# con-left-top.net
KiCad netlist of a schematic drawn in Altium Designer
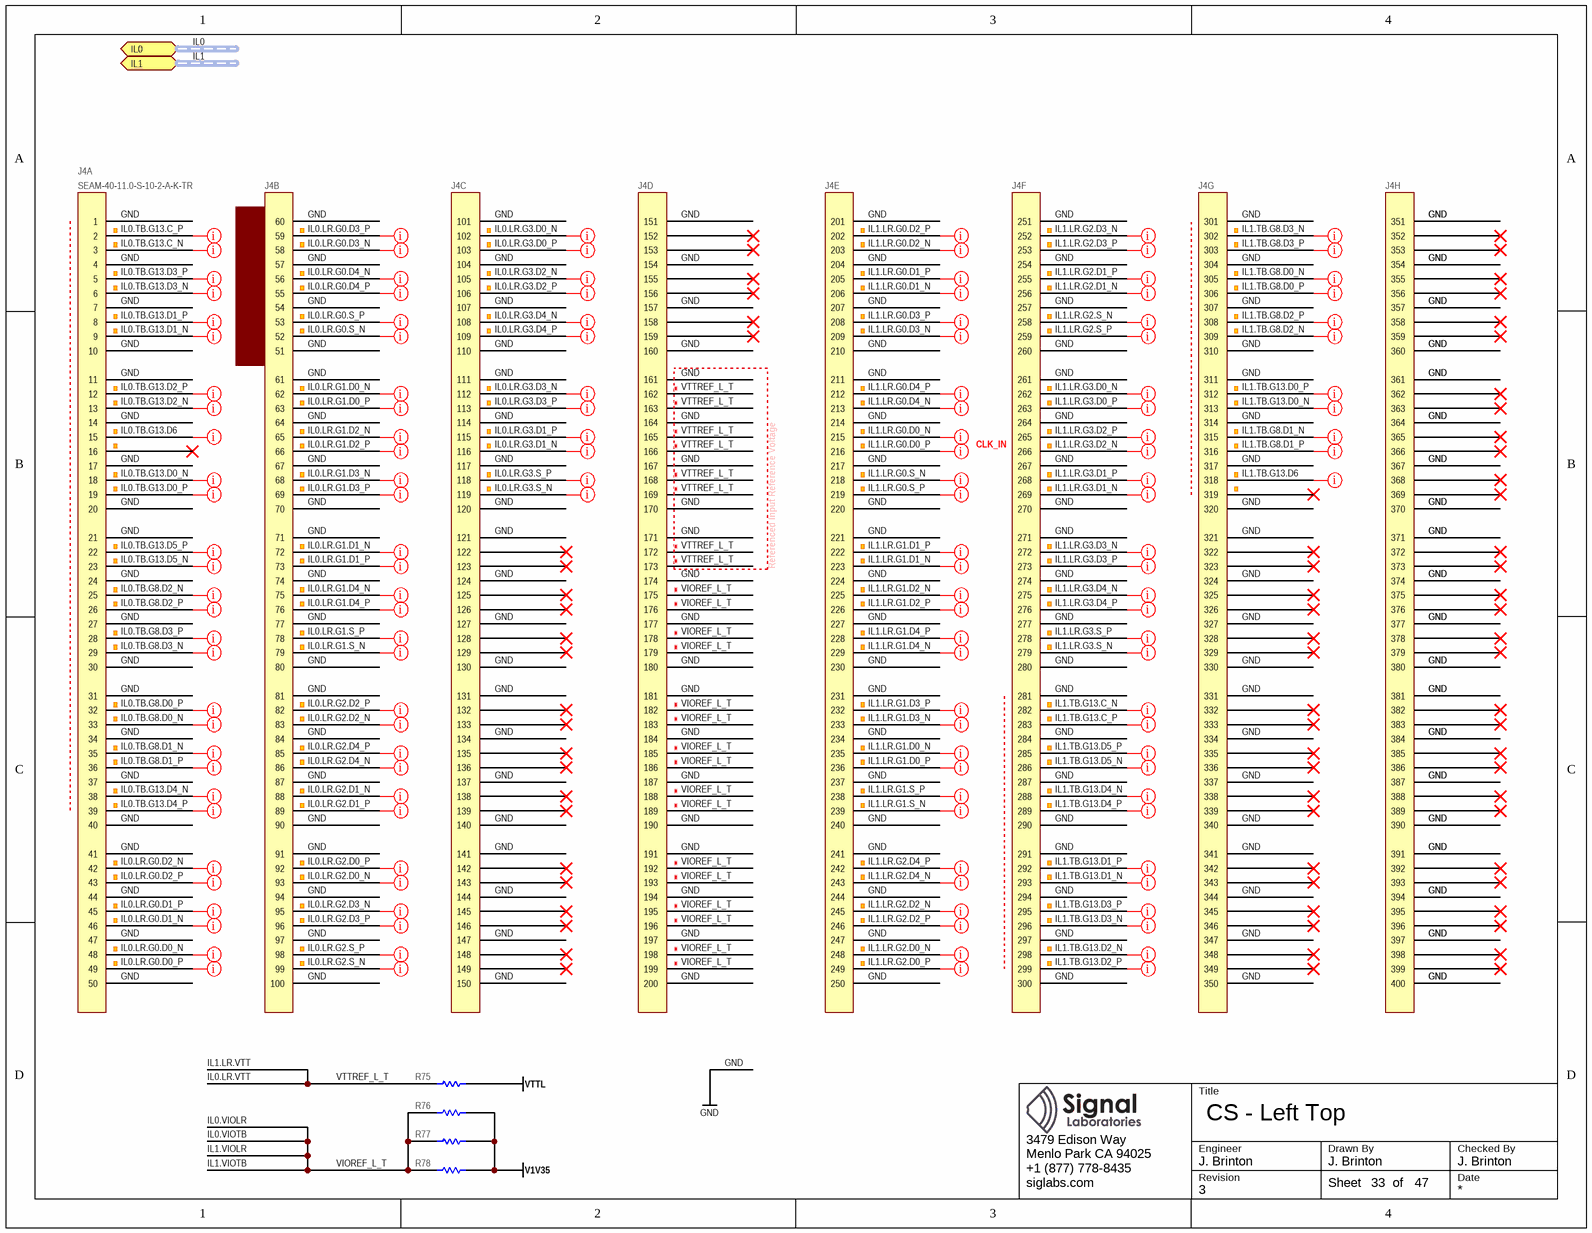
[diagram p0: con-left-top.SchDoc]

(export (version "E")
  (design (tool "Eeschema 10.0.6"))
  (components
    (comp (ref "J4")
      (value "SEAM-40-11.0-S-10-2-A-K-TR")
      (footprint "samtec:SEAM-40-11.0-S-10-2-A-K-TR")
      (description "Terminal Array Assembly, Surface Mount, 0.050\" Pitch, 400 Pins")
      (fields (field (name "MANUFACTURER") "Samtec"))
      (libsource (lib "samtec") (part "SEAM-40-11.0-S-10-2-A-K-TR"))
    )
    (comp (ref "R75")
      (value "SOLDER_LINK")
      (footprint "SOLDERLINK0603X26N")
      (description "Solder Link")
      (libsource (lib "generic") (part "RES"))
    )
    (comp (ref "R76")
      (value "SOLDER_LINK")
      (footprint "SOLDERLINK0603X26N")
      (description "Solder Link")
      (libsource (lib "generic") (part "RES"))
    )
    (comp (ref "R77")
      (value "SOLDER_LINK")
      (footprint "SOLDERLINK0603X26N")
      (description "Solder Link")
      (libsource (lib "generic") (part "RES"))
    )
    (comp (ref "R78")
      (value "SOLDER_LINK")
      (footprint "SOLDERLINK0603X26N")
      (description "Solder Link")
      (libsource (lib "generic") (part "RES"))
    )
  )
  (nets
    (net (code "3") (name "/IL0.LR.G0.D0_N") (class "Default")
      (node (ref "J4") (pin "48") (pinfunction "48_48") (pintype "passive"))
    )
    (net (code "4") (name "/IL0.LR.G0.D0_P") (class "Default")
      (node (ref "J4") (pin "49") (pinfunction "49_49") (pintype "passive"))
    )
    (net (code "5") (name "/IL0.LR.G0.D1_N") (class "Default")
      (node (ref "J4") (pin "46") (pinfunction "46_46") (pintype "passive"))
    )
    (net (code "6") (name "/IL0.LR.G0.D1_P") (class "Default")
      (node (ref "J4") (pin "45") (pinfunction "45_45") (pintype "passive"))
    )
    (net (code "7") (name "/IL0.LR.G0.D2_N") (class "Default")
      (node (ref "J4") (pin "42") (pinfunction "42_42") (pintype "passive"))
    )
    (net (code "8") (name "/IL0.LR.G0.D2_P") (class "Default")
      (node (ref "J4") (pin "43") (pinfunction "43_43") (pintype "passive"))
    )
    (net (code "9") (name "/IL0.LR.G0.D3_N") (class "Default")
      (node (ref "J4") (pin "58") (pinfunction "58_58") (pintype "passive"))
    )
    (net (code "10") (name "/IL0.LR.G0.D3_P") (class "Default")
      (node (ref "J4") (pin "59") (pinfunction "59_59") (pintype "passive"))
    )
    (net (code "11") (name "/IL0.LR.G0.D4_N") (class "Default")
      (node (ref "J4") (pin "56") (pinfunction "56_56") (pintype "passive"))
    )
    (net (code "12") (name "/IL0.LR.G0.D4_P") (class "Default")
      (node (ref "J4") (pin "55") (pinfunction "55_55") (pintype "passive"))
    )
    (net (code "13") (name "/IL0.LR.G0.S_N") (class "Default")
      (node (ref "J4") (pin "52") (pinfunction "52_52") (pintype "passive"))
    )
    (net (code "14") (name "/IL0.LR.G0.S_P") (class "Default")
      (node (ref "J4") (pin "53") (pinfunction "53_53") (pintype "passive"))
    )
    (net (code "15") (name "/IL0.LR.G1.D0_N") (class "Default")
      (node (ref "J4") (pin "62") (pinfunction "62_62") (pintype "passive"))
    )
    (net (code "16") (name "/IL0.LR.G1.D0_P") (class "Default")
      (node (ref "J4") (pin "63") (pinfunction "63_63") (pintype "passive"))
    )
    (net (code "17") (name "/IL0.LR.G1.D1_N") (class "Default")
      (node (ref "J4") (pin "72") (pinfunction "72_72") (pintype "passive"))
    )
    (net (code "18") (name "/IL0.LR.G1.D1_P") (class "Default")
      (node (ref "J4") (pin "73") (pinfunction "73_73") (pintype "passive"))
    )
    (net (code "19") (name "/IL0.LR.G1.D2_N") (class "Default")
      (node (ref "J4") (pin "65") (pinfunction "65_65") (pintype "passive"))
    )
    (net (code "20") (name "/IL0.LR.G1.D2_P") (class "Default")
      (node (ref "J4") (pin "66") (pinfunction "66_66") (pintype "passive"))
    )
    (net (code "21") (name "/IL0.LR.G1.D3_N") (class "Default")
      (node (ref "J4") (pin "68") (pinfunction "68_68") (pintype "passive"))
    )
    (net (code "22") (name "/IL0.LR.G1.D3_P") (class "Default")
      (node (ref "J4") (pin "69") (pinfunction "69_69") (pintype "passive"))
    )
    (net (code "23") (name "/IL0.LR.G1.D4_N") (class "Default")
      (node (ref "J4") (pin "75") (pinfunction "75_75") (pintype "passive"))
    )
    (net (code "24") (name "/IL0.LR.G1.D4_P") (class "Default")
      (node (ref "J4") (pin "76") (pinfunction "76_76") (pintype "passive"))
    )
    (net (code "25") (name "/IL0.LR.G1.S_N") (class "Default")
      (node (ref "J4") (pin "79") (pinfunction "79_79") (pintype "passive"))
    )
    (net (code "26") (name "/IL0.LR.G1.S_P") (class "Default")
      (node (ref "J4") (pin "78") (pinfunction "78_78") (pintype "passive"))
    )
    (net (code "27") (name "/IL0.LR.G2.D0_N") (class "Default")
      (node (ref "J4") (pin "93") (pinfunction "93_93") (pintype "passive"))
    )
    (net (code "28") (name "/IL0.LR.G2.D0_P") (class "Default")
      (node (ref "J4") (pin "92") (pinfunction "92_92") (pintype "passive"))
    )
    (net (code "29") (name "/IL0.LR.G2.D1_N") (class "Default")
      (node (ref "J4") (pin "88") (pinfunction "88_88") (pintype "passive"))
    )
    (net (code "30") (name "/IL0.LR.G2.D1_P") (class "Default")
      (node (ref "J4") (pin "89") (pinfunction "89_89") (pintype "passive"))
    )
    (net (code "31") (name "/IL0.LR.G2.D2_N") (class "Default")
      (node (ref "J4") (pin "83") (pinfunction "83_83") (pintype "passive"))
    )
    (net (code "32") (name "/IL0.LR.G2.D2_P") (class "Default")
      (node (ref "J4") (pin "82") (pinfunction "82_82") (pintype "passive"))
    )
    (net (code "33") (name "/IL0.LR.G2.D3_N") (class "Default")
      (node (ref "J4") (pin "95") (pinfunction "95_95") (pintype "passive"))
    )
    (net (code "34") (name "/IL0.LR.G2.D3_P") (class "Default")
      (node (ref "J4") (pin "96") (pinfunction "96_96") (pintype "passive"))
    )
    (net (code "35") (name "/IL0.LR.G2.D4_N") (class "Default")
      (node (ref "J4") (pin "86") (pinfunction "86_86") (pintype "passive"))
    )
    (net (code "36") (name "/IL0.LR.G2.D4_P") (class "Default")
      (node (ref "J4") (pin "85") (pinfunction "85_85") (pintype "passive"))
    )
    (net (code "37") (name "/IL0.LR.G2.S_N") (class "Default")
      (node (ref "J4") (pin "99") (pinfunction "99_99") (pintype "passive"))
    )
    (net (code "38") (name "/IL0.LR.G2.S_P") (class "Default")
      (node (ref "J4") (pin "98") (pinfunction "98_98") (pintype "passive"))
    )
    (net (code "39") (name "/IL0.LR.G3.D0_N") (class "Default")
      (node (ref "J4") (pin "102") (pinfunction "102_102") (pintype "passive"))
    )
    (net (code "40") (name "/IL0.LR.G3.D0_P") (class "Default")
      (node (ref "J4") (pin "103") (pinfunction "103_103") (pintype "passive"))
    )
    (net (code "41") (name "/IL0.LR.G3.D1_N") (class "Default")
      (node (ref "J4") (pin "116") (pinfunction "116_116") (pintype "passive"))
    )
    (net (code "42") (name "/IL0.LR.G3.D1_P") (class "Default")
      (node (ref "J4") (pin "115") (pinfunction "115_115") (pintype "passive"))
    )
    (net (code "43") (name "/IL0.LR.G3.D2_N") (class "Default")
      (node (ref "J4") (pin "105") (pinfunction "105_105") (pintype "passive"))
    )
    (net (code "44") (name "/IL0.LR.G3.D2_P") (class "Default")
      (node (ref "J4") (pin "106") (pinfunction "106_106") (pintype "passive"))
    )
    (net (code "45") (name "/IL0.LR.G3.D3_N") (class "Default")
      (node (ref "J4") (pin "112") (pinfunction "112_112") (pintype "passive"))
    )
    (net (code "46") (name "/IL0.LR.G3.D3_P") (class "Default")
      (node (ref "J4") (pin "113") (pinfunction "113_113") (pintype "passive"))
    )
    (net (code "47") (name "/IL0.LR.G3.D4_N") (class "Default")
      (node (ref "J4") (pin "108") (pinfunction "108_108") (pintype "passive"))
    )
    (net (code "48") (name "/IL0.LR.G3.D4_P") (class "Default")
      (node (ref "J4") (pin "109") (pinfunction "109_109") (pintype "passive"))
    )
    (net (code "49") (name "/IL0.LR.G3.S_N") (class "Default")
      (node (ref "J4") (pin "119") (pinfunction "119_119") (pintype "passive"))
    )
    (net (code "50") (name "/IL0.LR.G3.S_P") (class "Default")
      (node (ref "J4") (pin "118") (pinfunction "118_118") (pintype "passive"))
    )
    (net (code "51") (name "/IL0.LR.VTT") (class "Default")
      (node (ref "J4") (pin "162") (pinfunction "162_162") (pintype "passive"))
      (node (ref "J4") (pin "163") (pinfunction "163_163") (pintype "passive"))
      (node (ref "J4") (pin "165") (pinfunction "165_165") (pintype "passive"))
      (node (ref "J4") (pin "166") (pinfunction "166_166") (pintype "passive"))
      (node (ref "J4") (pin "168") (pinfunction "168_168") (pintype "passive"))
      (node (ref "J4") (pin "169") (pinfunction "169_169") (pintype "passive"))
      (node (ref "J4") (pin "172") (pinfunction "172_172") (pintype "passive"))
      (node (ref "J4") (pin "173") (pinfunction "173_173") (pintype "passive"))
      (node (ref "R75") (pin "2") (pinfunction "2_2") (pintype "passive"))
    )
    (net (code "52") (name "/IL0.TB.G8.D0_N") (class "Default")
      (node (ref "J4") (pin "33") (pinfunction "33_33") (pintype "passive"))
    )
    (net (code "53") (name "/IL0.TB.G8.D0_P") (class "Default")
      (node (ref "J4") (pin "32") (pinfunction "32_32") (pintype "passive"))
    )
    (net (code "54") (name "/IL0.TB.G8.D1_N") (class "Default")
      (node (ref "J4") (pin "35") (pinfunction "35_35") (pintype "passive"))
    )
    (net (code "55") (name "/IL0.TB.G8.D1_P") (class "Default")
      (node (ref "J4") (pin "36") (pinfunction "36_36") (pintype "passive"))
    )
    (net (code "56") (name "/IL0.TB.G8.D2_N") (class "Default")
      (node (ref "J4") (pin "25") (pinfunction "25_25") (pintype "passive"))
    )
    (net (code "57") (name "/IL0.TB.G8.D2_P") (class "Default")
      (node (ref "J4") (pin "26") (pinfunction "26_26") (pintype "passive"))
    )
    (net (code "58") (name "/IL0.TB.G8.D3_N") (class "Default")
      (node (ref "J4") (pin "29") (pinfunction "29_29") (pintype "passive"))
    )
    (net (code "59") (name "/IL0.TB.G8.D3_P") (class "Default")
      (node (ref "J4") (pin "28") (pinfunction "28_28") (pintype "passive"))
    )
    (net (code "60") (name "/IL0.TB.G13.C_N") (class "Default")
      (node (ref "J4") (pin "3") (pinfunction "3_3") (pintype "passive"))
    )
    (net (code "61") (name "/IL0.TB.G13.C_P") (class "Default")
      (node (ref "J4") (pin "2") (pinfunction "2_2") (pintype "passive"))
    )
    (net (code "62") (name "/IL0.TB.G13.D0_N") (class "Default")
      (node (ref "J4") (pin "18") (pinfunction "18_18") (pintype "passive"))
    )
    (net (code "63") (name "/IL0.TB.G13.D0_P") (class "Default")
      (node (ref "J4") (pin "19") (pinfunction "19_19") (pintype "passive"))
    )
    (net (code "64") (name "/IL0.TB.G13.D1_N") (class "Default")
      (node (ref "J4") (pin "9") (pinfunction "9_9") (pintype "passive"))
    )
    (net (code "65") (name "/IL0.TB.G13.D1_P") (class "Default")
      (node (ref "J4") (pin "8") (pinfunction "8_8") (pintype "passive"))
    )
    (net (code "66") (name "/IL0.TB.G13.D2_N") (class "Default")
      (node (ref "J4") (pin "13") (pinfunction "13_13") (pintype "passive"))
    )
    (net (code "67") (name "/IL0.TB.G13.D2_P") (class "Default")
      (node (ref "J4") (pin "12") (pinfunction "12_12") (pintype "passive"))
    )
    (net (code "68") (name "/IL0.TB.G13.D3_N") (class "Default")
      (node (ref "J4") (pin "6") (pinfunction "6_6") (pintype "passive"))
    )
    (net (code "69") (name "/IL0.TB.G13.D3_P") (class "Default")
      (node (ref "J4") (pin "5") (pinfunction "5_5") (pintype "passive"))
    )
    (net (code "70") (name "/IL0.TB.G13.D4_N") (class "Default")
      (node (ref "J4") (pin "38") (pinfunction "38_38") (pintype "passive"))
    )
    (net (code "71") (name "/IL0.TB.G13.D4_P") (class "Default")
      (node (ref "J4") (pin "39") (pinfunction "39_39") (pintype "passive"))
    )
    (net (code "72") (name "/IL0.TB.G13.D5_N") (class "Default")
      (node (ref "J4") (pin "23") (pinfunction "23_23") (pintype "passive"))
    )
    (net (code "73") (name "/IL0.TB.G13.D5_P") (class "Default")
      (node (ref "J4") (pin "22") (pinfunction "22_22") (pintype "passive"))
    )
    (net (code "74") (name "/IL0.TB.G13.D6") (class "Default")
      (node (ref "J4") (pin "15") (pinfunction "15_15") (pintype "passive"))
    )
    (net (code "75") (name "/IL0.VIOLR") (class "Default")
      (node (ref "J4") (pin "175") (pinfunction "175_175") (pintype "passive"))
      (node (ref "J4") (pin "176") (pinfunction "176_176") (pintype "passive"))
      (node (ref "J4") (pin "178") (pinfunction "178_178") (pintype "passive"))
      (node (ref "J4") (pin "179") (pinfunction "179_179") (pintype "passive"))
      (node (ref "J4") (pin "182") (pinfunction "182_182") (pintype "passive"))
      (node (ref "J4") (pin "183") (pinfunction "183_183") (pintype "passive"))
      (node (ref "J4") (pin "185") (pinfunction "185_185") (pintype "passive"))
      (node (ref "J4") (pin "186") (pinfunction "186_186") (pintype "passive"))
      (node (ref "J4") (pin "188") (pinfunction "188_188") (pintype "passive"))
      (node (ref "J4") (pin "189") (pinfunction "189_189") (pintype "passive"))
      (node (ref "J4") (pin "192") (pinfunction "192_192") (pintype "passive"))
      (node (ref "J4") (pin "193") (pinfunction "193_193") (pintype "passive"))
      (node (ref "J4") (pin "195") (pinfunction "195_195") (pintype "passive"))
      (node (ref "J4") (pin "196") (pinfunction "196_196") (pintype "passive"))
      (node (ref "J4") (pin "198") (pinfunction "198_198") (pintype "passive"))
      (node (ref "J4") (pin "199") (pinfunction "199_199") (pintype "passive"))
      (node (ref "R76") (pin "2") (pinfunction "2_2") (pintype "passive"))
      (node (ref "R77") (pin "2") (pinfunction "2_2") (pintype "passive"))
      (node (ref "R78") (pin "2") (pinfunction "2_2") (pintype "passive"))
    )
    (net (code "76") (name "/IL1.LR.G0.D0_N") (class "Default")
      (node (ref "J4") (pin "215") (pinfunction "215_215") (pintype "passive"))
    )
    (net (code "77") (name "/IL1.LR.G0.D0_P") (class "Default")
      (node (ref "J4") (pin "216") (pinfunction "216_216") (pintype "passive"))
    )
    (net (code "78") (name "/IL1.LR.G0.D1_N") (class "Default")
      (node (ref "J4") (pin "206") (pinfunction "206_206") (pintype "passive"))
    )
    (net (code "79") (name "/IL1.LR.G0.D1_P") (class "Default")
      (node (ref "J4") (pin "205") (pinfunction "205_205") (pintype "passive"))
    )
    (net (code "80") (name "/IL1.LR.G0.D2_N") (class "Default")
      (node (ref "J4") (pin "203") (pinfunction "203_203") (pintype "passive"))
    )
    (net (code "81") (name "/IL1.LR.G0.D2_P") (class "Default")
      (node (ref "J4") (pin "202") (pinfunction "202_202") (pintype "passive"))
    )
    (net (code "82") (name "/IL1.LR.G0.D3_N") (class "Default")
      (node (ref "J4") (pin "209") (pinfunction "209_209") (pintype "passive"))
    )
    (net (code "83") (name "/IL1.LR.G0.D3_P") (class "Default")
      (node (ref "J4") (pin "208") (pinfunction "208_208") (pintype "passive"))
    )
    (net (code "84") (name "/IL1.LR.G0.D4_N") (class "Default")
      (node (ref "J4") (pin "213") (pinfunction "213_213") (pintype "passive"))
    )
    (net (code "85") (name "/IL1.LR.G0.D4_P") (class "Default")
      (node (ref "J4") (pin "212") (pinfunction "212_212") (pintype "passive"))
    )
    (net (code "86") (name "/IL1.LR.G0.S_N") (class "Default")
      (node (ref "J4") (pin "218") (pinfunction "218_218") (pintype "passive"))
    )
    (net (code "87") (name "/IL1.LR.G0.S_P") (class "Default")
      (node (ref "J4") (pin "219") (pinfunction "219_219") (pintype "passive"))
    )
    (net (code "88") (name "/IL1.LR.G1.D0_N") (class "Default")
      (node (ref "J4") (pin "235") (pinfunction "235_235") (pintype "passive"))
    )
    (net (code "89") (name "/IL1.LR.G1.D0_P") (class "Default")
      (node (ref "J4") (pin "236") (pinfunction "236_236") (pintype "passive"))
    )
    (net (code "90") (name "/IL1.LR.G1.D1_N") (class "Default")
      (node (ref "J4") (pin "223") (pinfunction "223_223") (pintype "passive"))
    )
    (net (code "91") (name "/IL1.LR.G1.D1_P") (class "Default")
      (node (ref "J4") (pin "222") (pinfunction "222_222") (pintype "passive"))
    )
    (net (code "92") (name "/IL1.LR.G1.D2_N") (class "Default")
      (node (ref "J4") (pin "225") (pinfunction "225_225") (pintype "passive"))
    )
    (net (code "93") (name "/IL1.LR.G1.D2_P") (class "Default")
      (node (ref "J4") (pin "226") (pinfunction "226_226") (pintype "passive"))
    )
    (net (code "94") (name "/IL1.LR.G1.D3_N") (class "Default")
      (node (ref "J4") (pin "233") (pinfunction "233_233") (pintype "passive"))
    )
    (net (code "95") (name "/IL1.LR.G1.D3_P") (class "Default")
      (node (ref "J4") (pin "232") (pinfunction "232_232") (pintype "passive"))
    )
    (net (code "96") (name "/IL1.LR.G1.D4_N") (class "Default")
      (node (ref "J4") (pin "229") (pinfunction "229_229") (pintype "passive"))
    )
    (net (code "97") (name "/IL1.LR.G1.D4_P") (class "Default")
      (node (ref "J4") (pin "228") (pinfunction "228_228") (pintype "passive"))
    )
    (net (code "98") (name "/IL1.LR.G1.S_N") (class "Default")
      (node (ref "J4") (pin "239") (pinfunction "239_239") (pintype "passive"))
    )
    (net (code "99") (name "/IL1.LR.G1.S_P") (class "Default")
      (node (ref "J4") (pin "238") (pinfunction "238_238") (pintype "passive"))
    )
    (net (code "100") (name "/IL1.LR.G2.D0_N") (class "Default")
      (node (ref "J4") (pin "248") (pinfunction "248_248") (pintype "passive"))
    )
    (net (code "101") (name "/IL1.LR.G2.D0_P") (class "Default")
      (node (ref "J4") (pin "249") (pinfunction "249_249") (pintype "passive"))
    )
    (net (code "102") (name "/IL1.LR.G2.D1_N") (class "Default")
      (node (ref "J4") (pin "256") (pinfunction "256_256") (pintype "passive"))
    )
    (net (code "103") (name "/IL1.LR.G2.D1_P") (class "Default")
      (node (ref "J4") (pin "255") (pinfunction "255_255") (pintype "passive"))
    )
    (net (code "104") (name "/IL1.LR.G2.D2_N") (class "Default")
      (node (ref "J4") (pin "245") (pinfunction "245_245") (pintype "passive"))
    )
    (net (code "105") (name "/IL1.LR.G2.D2_P") (class "Default")
      (node (ref "J4") (pin "246") (pinfunction "246_246") (pintype "passive"))
    )
    (net (code "106") (name "/IL1.LR.G2.D3_N") (class "Default")
      (node (ref "J4") (pin "252") (pinfunction "252_252") (pintype "passive"))
    )
    (net (code "107") (name "/IL1.LR.G2.D3_P") (class "Default")
      (node (ref "J4") (pin "253") (pinfunction "253_253") (pintype "passive"))
    )
    (net (code "108") (name "/IL1.LR.G2.D4_N") (class "Default")
      (node (ref "J4") (pin "243") (pinfunction "243_243") (pintype "passive"))
    )
    (net (code "109") (name "/IL1.LR.G2.D4_P") (class "Default")
      (node (ref "J4") (pin "242") (pinfunction "242_242") (pintype "passive"))
    )
    (net (code "110") (name "/IL1.LR.G2.S_N") (class "Default")
      (node (ref "J4") (pin "258") (pinfunction "258_258") (pintype "passive"))
    )
    (net (code "111") (name "/IL1.LR.G2.S_P") (class "Default")
      (node (ref "J4") (pin "259") (pinfunction "259_259") (pintype "passive"))
    )
    (net (code "112") (name "/IL1.LR.G3.D0_N") (class "Default")
      (node (ref "J4") (pin "262") (pinfunction "262_262") (pintype "passive"))
    )
    (net (code "113") (name "/IL1.LR.G3.D0_P") (class "Default")
      (node (ref "J4") (pin "263") (pinfunction "263_263") (pintype "passive"))
    )
    (net (code "114") (name "/IL1.LR.G3.D1_N") (class "Default")
      (node (ref "J4") (pin "269") (pinfunction "269_269") (pintype "passive"))
    )
    (net (code "115") (name "/IL1.LR.G3.D1_P") (class "Default")
      (node (ref "J4") (pin "268") (pinfunction "268_268") (pintype "passive"))
    )
    (net (code "116") (name "/IL1.LR.G3.D2_N") (class "Default")
      (node (ref "J4") (pin "266") (pinfunction "266_266") (pintype "passive"))
    )
    (net (code "117") (name "/IL1.LR.G3.D2_P") (class "Default")
      (node (ref "J4") (pin "265") (pinfunction "265_265") (pintype "passive"))
    )
    (net (code "118") (name "/IL1.LR.G3.D3_N") (class "Default")
      (node (ref "J4") (pin "272") (pinfunction "272_272") (pintype "passive"))
    )
    (net (code "119") (name "/IL1.LR.G3.D3_P") (class "Default")
      (node (ref "J4") (pin "273") (pinfunction "273_273") (pintype "passive"))
    )
    (net (code "120") (name "/IL1.LR.G3.D4_N") (class "Default")
      (node (ref "J4") (pin "275") (pinfunction "275_275") (pintype "passive"))
    )
    (net (code "121") (name "/IL1.LR.G3.D4_P") (class "Default")
      (node (ref "J4") (pin "276") (pinfunction "276_276") (pintype "passive"))
    )
    (net (code "122") (name "/IL1.LR.G3.S_N") (class "Default")
      (node (ref "J4") (pin "279") (pinfunction "279_279") (pintype "passive"))
    )
    (net (code "123") (name "/IL1.LR.G3.S_P") (class "Default")
      (node (ref "J4") (pin "278") (pinfunction "278_278") (pintype "passive"))
    )
    (net (code "124") (name "/IL1.TB.G8.D0_N") (class "Default")
      (node (ref "J4") (pin "305") (pinfunction "305_305") (pintype "passive"))
    )
    (net (code "125") (name "/IL1.TB.G8.D0_P") (class "Default")
      (node (ref "J4") (pin "306") (pinfunction "306_306") (pintype "passive"))
    )
    (net (code "126") (name "/IL1.TB.G8.D1_N") (class "Default")
      (node (ref "J4") (pin "315") (pinfunction "315_315") (pintype "passive"))
    )
    (net (code "127") (name "/IL1.TB.G8.D1_P") (class "Default")
      (node (ref "J4") (pin "316") (pinfunction "316_316") (pintype "passive"))
    )
    (net (code "128") (name "/IL1.TB.G8.D2_N") (class "Default")
      (node (ref "J4") (pin "309") (pinfunction "309_309") (pintype "passive"))
    )
    (net (code "129") (name "/IL1.TB.G8.D2_P") (class "Default")
      (node (ref "J4") (pin "308") (pinfunction "308_308") (pintype "passive"))
    )
    (net (code "130") (name "/IL1.TB.G8.D3_N") (class "Default")
      (node (ref "J4") (pin "302") (pinfunction "302_302") (pintype "passive"))
    )
    (net (code "131") (name "/IL1.TB.G8.D3_P") (class "Default")
      (node (ref "J4") (pin "303") (pinfunction "303_303") (pintype "passive"))
    )
    (net (code "132") (name "/IL1.TB.G13.C_N") (class "Default")
      (node (ref "J4") (pin "282") (pinfunction "282_282") (pintype "passive"))
    )
    (net (code "133") (name "/IL1.TB.G13.C_P") (class "Default")
      (node (ref "J4") (pin "283") (pinfunction "283_283") (pintype "passive"))
    )
    (net (code "134") (name "/IL1.TB.G13.D0_N") (class "Default")
      (node (ref "J4") (pin "313") (pinfunction "313_313") (pintype "passive"))
    )
    (net (code "135") (name "/IL1.TB.G13.D0_P") (class "Default")
      (node (ref "J4") (pin "312") (pinfunction "312_312") (pintype "passive"))
    )
    (net (code "136") (name "/IL1.TB.G13.D1_N") (class "Default")
      (node (ref "J4") (pin "293") (pinfunction "293_293") (pintype "passive"))
    )
    (net (code "137") (name "/IL1.TB.G13.D1_P") (class "Default")
      (node (ref "J4") (pin "292") (pinfunction "292_292") (pintype "passive"))
    )
    (net (code "138") (name "/IL1.TB.G13.D2_N") (class "Default")
      (node (ref "J4") (pin "298") (pinfunction "298_298") (pintype "passive"))
    )
    (net (code "139") (name "/IL1.TB.G13.D2_P") (class "Default")
      (node (ref "J4") (pin "299") (pinfunction "299_299") (pintype "passive"))
    )
    (net (code "140") (name "/IL1.TB.G13.D3_N") (class "Default")
      (node (ref "J4") (pin "296") (pinfunction "296_296") (pintype "passive"))
    )
    (net (code "141") (name "/IL1.TB.G13.D3_P") (class "Default")
      (node (ref "J4") (pin "295") (pinfunction "295_295") (pintype "passive"))
    )
    (net (code "142") (name "/IL1.TB.G13.D4_N") (class "Default")
      (node (ref "J4") (pin "288") (pinfunction "288_288") (pintype "passive"))
    )
    (net (code "143") (name "/IL1.TB.G13.D4_P") (class "Default")
      (node (ref "J4") (pin "289") (pinfunction "289_289") (pintype "passive"))
    )
    (net (code "144") (name "/IL1.TB.G13.D5_N") (class "Default")
      (node (ref "J4") (pin "286") (pinfunction "286_286") (pintype "passive"))
    )
    (net (code "145") (name "/IL1.TB.G13.D5_P") (class "Default")
      (node (ref "J4") (pin "285") (pinfunction "285_285") (pintype "passive"))
    )
    (net (code "146") (name "/IL1.TB.G13.D6") (class "Default")
      (node (ref "J4") (pin "318") (pinfunction "318_318") (pintype "passive"))
    )
    (net (code "149") (name "GND") (class "Default")
      (node (ref "J4") (pin "1") (pinfunction "1_1") (pintype "passive"))
      (node (ref "J4") (pin "10") (pinfunction "10_10") (pintype "passive"))
      (node (ref "J4") (pin "100") (pinfunction "100_100") (pintype "passive"))
      (node (ref "J4") (pin "101") (pinfunction "101_101") (pintype "passive"))
      (node (ref "J4") (pin "104") (pinfunction "104_104") (pintype "passive"))
      (node (ref "J4") (pin "107") (pinfunction "107_107") (pintype "passive"))
      (node (ref "J4") (pin "11") (pinfunction "11_11") (pintype "passive"))
      (node (ref "J4") (pin "110") (pinfunction "110_110") (pintype "passive"))
      (node (ref "J4") (pin "111") (pinfunction "111_111") (pintype "passive"))
      (node (ref "J4") (pin "114") (pinfunction "114_114") (pintype "passive"))
      (node (ref "J4") (pin "117") (pinfunction "117_117") (pintype "passive"))
      (node (ref "J4") (pin "120") (pinfunction "120_120") (pintype "passive"))
      (node (ref "J4") (pin "121") (pinfunction "121_121") (pintype "passive"))
      (node (ref "J4") (pin "124") (pinfunction "124_124") (pintype "passive"))
      (node (ref "J4") (pin "127") (pinfunction "127_127") (pintype "passive"))
      (node (ref "J4") (pin "130") (pinfunction "130_130") (pintype "passive"))
      (node (ref "J4") (pin "131") (pinfunction "131_131") (pintype "passive"))
      (node (ref "J4") (pin "134") (pinfunction "134_134") (pintype "passive"))
      (node (ref "J4") (pin "137") (pinfunction "137_137") (pintype "passive"))
      (node (ref "J4") (pin "14") (pinfunction "14_14") (pintype "passive"))
      (node (ref "J4") (pin "140") (pinfunction "140_140") (pintype "passive"))
      (node (ref "J4") (pin "141") (pinfunction "141_141") (pintype "passive"))
      (node (ref "J4") (pin "144") (pinfunction "144_144") (pintype "passive"))
      (node (ref "J4") (pin "147") (pinfunction "147_147") (pintype "passive"))
      (node (ref "J4") (pin "150") (pinfunction "150_150") (pintype "passive"))
      (node (ref "J4") (pin "151") (pinfunction "151_151") (pintype "passive"))
      (node (ref "J4") (pin "154") (pinfunction "154_154") (pintype "passive"))
      (node (ref "J4") (pin "157") (pinfunction "157_157") (pintype "passive"))
      (node (ref "J4") (pin "160") (pinfunction "160_160") (pintype "passive"))
      (node (ref "J4") (pin "161") (pinfunction "161_161") (pintype "passive"))
      (node (ref "J4") (pin "164") (pinfunction "164_164") (pintype "passive"))
      (node (ref "J4") (pin "167") (pinfunction "167_167") (pintype "passive"))
      (node (ref "J4") (pin "17") (pinfunction "17_17") (pintype "passive"))
      (node (ref "J4") (pin "170") (pinfunction "170_170") (pintype "passive"))
      (node (ref "J4") (pin "171") (pinfunction "171_171") (pintype "passive"))
      (node (ref "J4") (pin "174") (pinfunction "174_174") (pintype "passive"))
      (node (ref "J4") (pin "177") (pinfunction "177_177") (pintype "passive"))
      (node (ref "J4") (pin "180") (pinfunction "180_180") (pintype "passive"))
      (node (ref "J4") (pin "181") (pinfunction "181_181") (pintype "passive"))
      (node (ref "J4") (pin "184") (pinfunction "184_184") (pintype "passive"))
      (node (ref "J4") (pin "187") (pinfunction "187_187") (pintype "passive"))
      (node (ref "J4") (pin "190") (pinfunction "190_190") (pintype "passive"))
      (node (ref "J4") (pin "191") (pinfunction "191_191") (pintype "passive"))
      (node (ref "J4") (pin "194") (pinfunction "194_194") (pintype "passive"))
      (node (ref "J4") (pin "197") (pinfunction "197_197") (pintype "passive"))
      (node (ref "J4") (pin "20") (pinfunction "20_20") (pintype "passive"))
      (node (ref "J4") (pin "200") (pinfunction "200_200") (pintype "passive"))
      (node (ref "J4") (pin "201") (pinfunction "201_201") (pintype "passive"))
      (node (ref "J4") (pin "204") (pinfunction "204_204") (pintype "passive"))
      (node (ref "J4") (pin "207") (pinfunction "207_207") (pintype "passive"))
      (node (ref "J4") (pin "21") (pinfunction "21_21") (pintype "passive"))
      (node (ref "J4") (pin "210") (pinfunction "210_210") (pintype "passive"))
      (node (ref "J4") (pin "211") (pinfunction "211_211") (pintype "passive"))
      (node (ref "J4") (pin "214") (pinfunction "214_214") (pintype "passive"))
      (node (ref "J4") (pin "217") (pinfunction "217_217") (pintype "passive"))
      (node (ref "J4") (pin "220") (pinfunction "220_220") (pintype "passive"))
      (node (ref "J4") (pin "221") (pinfunction "221_221") (pintype "passive"))
      (node (ref "J4") (pin "224") (pinfunction "224_224") (pintype "passive"))
      (node (ref "J4") (pin "227") (pinfunction "227_227") (pintype "passive"))
      (node (ref "J4") (pin "230") (pinfunction "230_230") (pintype "passive"))
      (node (ref "J4") (pin "231") (pinfunction "231_231") (pintype "passive"))
      (node (ref "J4") (pin "234") (pinfunction "234_234") (pintype "passive"))
      (node (ref "J4") (pin "237") (pinfunction "237_237") (pintype "passive"))
      (node (ref "J4") (pin "24") (pinfunction "24_24") (pintype "passive"))
      (node (ref "J4") (pin "240") (pinfunction "240_240") (pintype "passive"))
      (node (ref "J4") (pin "241") (pinfunction "241_241") (pintype "passive"))
      (node (ref "J4") (pin "244") (pinfunction "244_244") (pintype "passive"))
      (node (ref "J4") (pin "247") (pinfunction "247_247") (pintype "passive"))
      (node (ref "J4") (pin "250") (pinfunction "250_250") (pintype "passive"))
      (node (ref "J4") (pin "251") (pinfunction "251_251") (pintype "passive"))
      (node (ref "J4") (pin "254") (pinfunction "254_254") (pintype "passive"))
      (node (ref "J4") (pin "257") (pinfunction "257_257") (pintype "passive"))
      (node (ref "J4") (pin "260") (pinfunction "260_260") (pintype "passive"))
      (node (ref "J4") (pin "261") (pinfunction "261_261") (pintype "passive"))
      (node (ref "J4") (pin "264") (pinfunction "264_264") (pintype "passive"))
      (node (ref "J4") (pin "267") (pinfunction "267_267") (pintype "passive"))
      (node (ref "J4") (pin "27") (pinfunction "27_27") (pintype "passive"))
      (node (ref "J4") (pin "270") (pinfunction "270_270") (pintype "passive"))
      (node (ref "J4") (pin "271") (pinfunction "271_271") (pintype "passive"))
      (node (ref "J4") (pin "274") (pinfunction "274_274") (pintype "passive"))
      (node (ref "J4") (pin "277") (pinfunction "277_277") (pintype "passive"))
      (node (ref "J4") (pin "280") (pinfunction "280_280") (pintype "passive"))
      (node (ref "J4") (pin "281") (pinfunction "281_281") (pintype "passive"))
      (node (ref "J4") (pin "284") (pinfunction "284_284") (pintype "passive"))
      (node (ref "J4") (pin "287") (pinfunction "287_287") (pintype "passive"))
      (node (ref "J4") (pin "290") (pinfunction "290_290") (pintype "passive"))
      (node (ref "J4") (pin "291") (pinfunction "291_291") (pintype "passive"))
      (node (ref "J4") (pin "294") (pinfunction "294_294") (pintype "passive"))
      (node (ref "J4") (pin "297") (pinfunction "297_297") (pintype "passive"))
      (node (ref "J4") (pin "30") (pinfunction "30_30") (pintype "passive"))
      (node (ref "J4") (pin "300") (pinfunction "300_300") (pintype "passive"))
      (node (ref "J4") (pin "301") (pinfunction "301_301") (pintype "passive"))
      (node (ref "J4") (pin "304") (pinfunction "304_304") (pintype "passive"))
      (node (ref "J4") (pin "307") (pinfunction "307_307") (pintype "passive"))
      (node (ref "J4") (pin "31") (pinfunction "31_31") (pintype "passive"))
      (node (ref "J4") (pin "310") (pinfunction "310_310") (pintype "passive"))
      (node (ref "J4") (pin "311") (pinfunction "311_311") (pintype "passive"))
      (node (ref "J4") (pin "314") (pinfunction "314_314") (pintype "passive"))
      (node (ref "J4") (pin "317") (pinfunction "317_317") (pintype "passive"))
      (node (ref "J4") (pin "320") (pinfunction "320_320") (pintype "passive"))
      (node (ref "J4") (pin "321") (pinfunction "321_321") (pintype "passive"))
      (node (ref "J4") (pin "324") (pinfunction "324_324") (pintype "passive"))
      (node (ref "J4") (pin "327") (pinfunction "327_327") (pintype "passive"))
      (node (ref "J4") (pin "330") (pinfunction "330_330") (pintype "passive"))
      (node (ref "J4") (pin "331") (pinfunction "331_331") (pintype "passive"))
      (node (ref "J4") (pin "334") (pinfunction "334_334") (pintype "passive"))
      (node (ref "J4") (pin "337") (pinfunction "337_337") (pintype "passive"))
      (node (ref "J4") (pin "34") (pinfunction "34_34") (pintype "passive"))
      (node (ref "J4") (pin "340") (pinfunction "340_340") (pintype "passive"))
      (node (ref "J4") (pin "341") (pinfunction "341_341") (pintype "passive"))
      (node (ref "J4") (pin "344") (pinfunction "344_344") (pintype "passive"))
      (node (ref "J4") (pin "347") (pinfunction "347_347") (pintype "passive"))
      (node (ref "J4") (pin "350") (pinfunction "350_350") (pintype "passive"))
      (node (ref "J4") (pin "351") (pinfunction "351_351") (pintype "passive"))
      (node (ref "J4") (pin "354") (pinfunction "354_354") (pintype "passive"))
      (node (ref "J4") (pin "357") (pinfunction "357_357") (pintype "passive"))
      (node (ref "J4") (pin "360") (pinfunction "360_360") (pintype "passive"))
      (node (ref "J4") (pin "361") (pinfunction "361_361") (pintype "passive"))
      (node (ref "J4") (pin "364") (pinfunction "364_364") (pintype "passive"))
      (node (ref "J4") (pin "367") (pinfunction "367_367") (pintype "passive"))
      (node (ref "J4") (pin "37") (pinfunction "37_37") (pintype "passive"))
      (node (ref "J4") (pin "370") (pinfunction "370_370") (pintype "passive"))
      (node (ref "J4") (pin "371") (pinfunction "371_371") (pintype "passive"))
      (node (ref "J4") (pin "374") (pinfunction "374_374") (pintype "passive"))
      (node (ref "J4") (pin "377") (pinfunction "377_377") (pintype "passive"))
      (node (ref "J4") (pin "380") (pinfunction "380_380") (pintype "passive"))
      (node (ref "J4") (pin "381") (pinfunction "381_381") (pintype "passive"))
      (node (ref "J4") (pin "384") (pinfunction "384_384") (pintype "passive"))
      (node (ref "J4") (pin "387") (pinfunction "387_387") (pintype "passive"))
      (node (ref "J4") (pin "390") (pinfunction "390_390") (pintype "passive"))
      (node (ref "J4") (pin "391") (pinfunction "391_391") (pintype "passive"))
      (node (ref "J4") (pin "394") (pinfunction "394_394") (pintype "passive"))
      (node (ref "J4") (pin "397") (pinfunction "397_397") (pintype "passive"))
      (node (ref "J4") (pin "4") (pinfunction "4_4") (pintype "passive"))
      (node (ref "J4") (pin "40") (pinfunction "40_40") (pintype "passive"))
      (node (ref "J4") (pin "400") (pinfunction "400_400") (pintype "passive"))
      (node (ref "J4") (pin "41") (pinfunction "41_41") (pintype "passive"))
      (node (ref "J4") (pin "44") (pinfunction "44_44") (pintype "passive"))
      (node (ref "J4") (pin "47") (pinfunction "47_47") (pintype "passive"))
      (node (ref "J4") (pin "50") (pinfunction "50_50") (pintype "passive"))
      (node (ref "J4") (pin "51") (pinfunction "51_51") (pintype "passive"))
      (node (ref "J4") (pin "54") (pinfunction "54_54") (pintype "passive"))
      (node (ref "J4") (pin "57") (pinfunction "57_57") (pintype "passive"))
      (node (ref "J4") (pin "60") (pinfunction "60_60") (pintype "passive"))
      (node (ref "J4") (pin "61") (pinfunction "61_61") (pintype "passive"))
      (node (ref "J4") (pin "64") (pinfunction "64_64") (pintype "passive"))
      (node (ref "J4") (pin "67") (pinfunction "67_67") (pintype "passive"))
      (node (ref "J4") (pin "7") (pinfunction "7_7") (pintype "passive"))
      (node (ref "J4") (pin "70") (pinfunction "70_70") (pintype "passive"))
      (node (ref "J4") (pin "71") (pinfunction "71_71") (pintype "passive"))
      (node (ref "J4") (pin "74") (pinfunction "74_74") (pintype "passive"))
      (node (ref "J4") (pin "77") (pinfunction "77_77") (pintype "passive"))
      (node (ref "J4") (pin "80") (pinfunction "80_80") (pintype "passive"))
      (node (ref "J4") (pin "81") (pinfunction "81_81") (pintype "passive"))
      (node (ref "J4") (pin "84") (pinfunction "84_84") (pintype "passive"))
      (node (ref "J4") (pin "87") (pinfunction "87_87") (pintype "passive"))
      (node (ref "J4") (pin "90") (pinfunction "90_90") (pintype "passive"))
      (node (ref "J4") (pin "91") (pinfunction "91_91") (pintype "passive"))
      (node (ref "J4") (pin "94") (pinfunction "94_94") (pintype "passive"))
      (node (ref "J4") (pin "97") (pinfunction "97_97") (pintype "passive"))
    )
    (net (code "150") (name "V1V35") (class "Default")
      (node (ref "R76") (pin "1") (pinfunction "1_1") (pintype "passive"))
      (node (ref "R77") (pin "1") (pinfunction "1_1") (pintype "passive"))
      (node (ref "R78") (pin "1") (pinfunction "1_1") (pintype "passive"))
    )
    (net (code "151") (name "VTTL") (class "Default")
      (node (ref "R75") (pin "1") (pinfunction "1_1") (pintype "passive"))
    )
    (net (code "152") (name "unconnected-(J4-Pad16)") (class "Default")
      (node (ref "J4") (pin "16") (pinfunction "16_16") (pintype "passive+no_connect"))
    )
    (net (code "153") (name "unconnected-(J4-Pad122)") (class "Default")
      (node (ref "J4") (pin "122") (pinfunction "122_122") (pintype "passive+no_connect"))
    )
    (net (code "154") (name "unconnected-(J4-Pad123)") (class "Default")
      (node (ref "J4") (pin "123") (pinfunction "123_123") (pintype "passive+no_connect"))
    )
    (net (code "155") (name "unconnected-(J4-Pad125)") (class "Default")
      (node (ref "J4") (pin "125") (pinfunction "125_125") (pintype "passive+no_connect"))
    )
    (net (code "156") (name "unconnected-(J4-Pad126)") (class "Default")
      (node (ref "J4") (pin "126") (pinfunction "126_126") (pintype "passive+no_connect"))
    )
    (net (code "157") (name "unconnected-(J4-Pad128)") (class "Default")
      (node (ref "J4") (pin "128") (pinfunction "128_128") (pintype "passive+no_connect"))
    )
    (net (code "158") (name "unconnected-(J4-Pad129)") (class "Default")
      (node (ref "J4") (pin "129") (pinfunction "129_129") (pintype "passive+no_connect"))
    )
    (net (code "159") (name "unconnected-(J4-Pad132)") (class "Default")
      (node (ref "J4") (pin "132") (pinfunction "132_132") (pintype "passive+no_connect"))
    )
    (net (code "160") (name "unconnected-(J4-Pad133)") (class "Default")
      (node (ref "J4") (pin "133") (pinfunction "133_133") (pintype "passive+no_connect"))
    )
    (net (code "161") (name "unconnected-(J4-Pad135)") (class "Default")
      (node (ref "J4") (pin "135") (pinfunction "135_135") (pintype "passive+no_connect"))
    )
    (net (code "162") (name "unconnected-(J4-Pad136)") (class "Default")
      (node (ref "J4") (pin "136") (pinfunction "136_136") (pintype "passive+no_connect"))
    )
    (net (code "163") (name "unconnected-(J4-Pad138)") (class "Default")
      (node (ref "J4") (pin "138") (pinfunction "138_138") (pintype "passive+no_connect"))
    )
    (net (code "164") (name "unconnected-(J4-Pad139)") (class "Default")
      (node (ref "J4") (pin "139") (pinfunction "139_139") (pintype "passive+no_connect"))
    )
    (net (code "165") (name "unconnected-(J4-Pad142)") (class "Default")
      (node (ref "J4") (pin "142") (pinfunction "142_142") (pintype "passive+no_connect"))
    )
    (net (code "166") (name "unconnected-(J4-Pad143)") (class "Default")
      (node (ref "J4") (pin "143") (pinfunction "143_143") (pintype "passive+no_connect"))
    )
    (net (code "167") (name "unconnected-(J4-Pad145)") (class "Default")
      (node (ref "J4") (pin "145") (pinfunction "145_145") (pintype "passive+no_connect"))
    )
    (net (code "168") (name "unconnected-(J4-Pad146)") (class "Default")
      (node (ref "J4") (pin "146") (pinfunction "146_146") (pintype "passive+no_connect"))
    )
    (net (code "169") (name "unconnected-(J4-Pad148)") (class "Default")
      (node (ref "J4") (pin "148") (pinfunction "148_148") (pintype "passive+no_connect"))
    )
    (net (code "170") (name "unconnected-(J4-Pad149)") (class "Default")
      (node (ref "J4") (pin "149") (pinfunction "149_149") (pintype "passive+no_connect"))
    )
    (net (code "171") (name "unconnected-(J4-Pad152)") (class "Default")
      (node (ref "J4") (pin "152") (pinfunction "152_152") (pintype "passive+no_connect"))
    )
    (net (code "172") (name "unconnected-(J4-Pad153)") (class "Default")
      (node (ref "J4") (pin "153") (pinfunction "153_153") (pintype "passive+no_connect"))
    )
    (net (code "173") (name "unconnected-(J4-Pad155)") (class "Default")
      (node (ref "J4") (pin "155") (pinfunction "155_155") (pintype "passive+no_connect"))
    )
    (net (code "174") (name "unconnected-(J4-Pad156)") (class "Default")
      (node (ref "J4") (pin "156") (pinfunction "156_156") (pintype "passive+no_connect"))
    )
    (net (code "175") (name "unconnected-(J4-Pad158)") (class "Default")
      (node (ref "J4") (pin "158") (pinfunction "158_158") (pintype "passive+no_connect"))
    )
    (net (code "176") (name "unconnected-(J4-Pad159)") (class "Default")
      (node (ref "J4") (pin "159") (pinfunction "159_159") (pintype "passive+no_connect"))
    )
    (net (code "177") (name "unconnected-(J4-Pad319)") (class "Default")
      (node (ref "J4") (pin "319") (pinfunction "319_319") (pintype "passive+no_connect"))
    )
    (net (code "178") (name "unconnected-(J4-Pad322)") (class "Default")
      (node (ref "J4") (pin "322") (pinfunction "322_322") (pintype "passive+no_connect"))
    )
    (net (code "179") (name "unconnected-(J4-Pad323)") (class "Default")
      (node (ref "J4") (pin "323") (pinfunction "323_323") (pintype "passive+no_connect"))
    )
    (net (code "180") (name "unconnected-(J4-Pad325)") (class "Default")
      (node (ref "J4") (pin "325") (pinfunction "325_325") (pintype "passive+no_connect"))
    )
    (net (code "181") (name "unconnected-(J4-Pad326)") (class "Default")
      (node (ref "J4") (pin "326") (pinfunction "326_326") (pintype "passive+no_connect"))
    )
    (net (code "182") (name "unconnected-(J4-Pad328)") (class "Default")
      (node (ref "J4") (pin "328") (pinfunction "328_328") (pintype "passive+no_connect"))
    )
    (net (code "183") (name "unconnected-(J4-Pad329)") (class "Default")
      (node (ref "J4") (pin "329") (pinfunction "329_329") (pintype "passive+no_connect"))
    )
    (net (code "184") (name "unconnected-(J4-Pad332)") (class "Default")
      (node (ref "J4") (pin "332") (pinfunction "332_332") (pintype "passive+no_connect"))
    )
    (net (code "185") (name "unconnected-(J4-Pad333)") (class "Default")
      (node (ref "J4") (pin "333") (pinfunction "333_333") (pintype "passive+no_connect"))
    )
    (net (code "186") (name "unconnected-(J4-Pad335)") (class "Default")
      (node (ref "J4") (pin "335") (pinfunction "335_335") (pintype "passive+no_connect"))
    )
    (net (code "187") (name "unconnected-(J4-Pad336)") (class "Default")
      (node (ref "J4") (pin "336") (pinfunction "336_336") (pintype "passive+no_connect"))
    )
    (net (code "188") (name "unconnected-(J4-Pad338)") (class "Default")
      (node (ref "J4") (pin "338") (pinfunction "338_338") (pintype "passive+no_connect"))
    )
    (net (code "189") (name "unconnected-(J4-Pad339)") (class "Default")
      (node (ref "J4") (pin "339") (pinfunction "339_339") (pintype "passive+no_connect"))
    )
    (net (code "190") (name "unconnected-(J4-Pad342)") (class "Default")
      (node (ref "J4") (pin "342") (pinfunction "342_342") (pintype "passive+no_connect"))
    )
    (net (code "191") (name "unconnected-(J4-Pad343)") (class "Default")
      (node (ref "J4") (pin "343") (pinfunction "343_343") (pintype "passive+no_connect"))
    )
    (net (code "192") (name "unconnected-(J4-Pad345)") (class "Default")
      (node (ref "J4") (pin "345") (pinfunction "345_345") (pintype "passive+no_connect"))
    )
    (net (code "193") (name "unconnected-(J4-Pad346)") (class "Default")
      (node (ref "J4") (pin "346") (pinfunction "346_346") (pintype "passive+no_connect"))
    )
    (net (code "194") (name "unconnected-(J4-Pad348)") (class "Default")
      (node (ref "J4") (pin "348") (pinfunction "348_348") (pintype "passive+no_connect"))
    )
    (net (code "195") (name "unconnected-(J4-Pad349)") (class "Default")
      (node (ref "J4") (pin "349") (pinfunction "349_349") (pintype "passive+no_connect"))
    )
    (net (code "196") (name "unconnected-(J4-Pad352)") (class "Default")
      (node (ref "J4") (pin "352") (pinfunction "352_352") (pintype "passive+no_connect"))
    )
    (net (code "197") (name "unconnected-(J4-Pad353)") (class "Default")
      (node (ref "J4") (pin "353") (pinfunction "353_353") (pintype "passive+no_connect"))
    )
    (net (code "198") (name "unconnected-(J4-Pad355)") (class "Default")
      (node (ref "J4") (pin "355") (pinfunction "355_355") (pintype "passive+no_connect"))
    )
    (net (code "199") (name "unconnected-(J4-Pad356)") (class "Default")
      (node (ref "J4") (pin "356") (pinfunction "356_356") (pintype "passive+no_connect"))
    )
    (net (code "200") (name "unconnected-(J4-Pad358)") (class "Default")
      (node (ref "J4") (pin "358") (pinfunction "358_358") (pintype "passive+no_connect"))
    )
    (net (code "201") (name "unconnected-(J4-Pad359)") (class "Default")
      (node (ref "J4") (pin "359") (pinfunction "359_359") (pintype "passive+no_connect"))
    )
    (net (code "202") (name "unconnected-(J4-Pad362)") (class "Default")
      (node (ref "J4") (pin "362") (pinfunction "362_362") (pintype "passive+no_connect"))
    )
    (net (code "203") (name "unconnected-(J4-Pad363)") (class "Default")
      (node (ref "J4") (pin "363") (pinfunction "363_363") (pintype "passive+no_connect"))
    )
    (net (code "204") (name "unconnected-(J4-Pad365)") (class "Default")
      (node (ref "J4") (pin "365") (pinfunction "365_365") (pintype "passive+no_connect"))
    )
    (net (code "205") (name "unconnected-(J4-Pad366)") (class "Default")
      (node (ref "J4") (pin "366") (pinfunction "366_366") (pintype "passive+no_connect"))
    )
    (net (code "206") (name "unconnected-(J4-Pad368)") (class "Default")
      (node (ref "J4") (pin "368") (pinfunction "368_368") (pintype "passive+no_connect"))
    )
    (net (code "207") (name "unconnected-(J4-Pad369)") (class "Default")
      (node (ref "J4") (pin "369") (pinfunction "369_369") (pintype "passive+no_connect"))
    )
    (net (code "208") (name "unconnected-(J4-Pad372)") (class "Default")
      (node (ref "J4") (pin "372") (pinfunction "372_372") (pintype "passive+no_connect"))
    )
    (net (code "209") (name "unconnected-(J4-Pad373)") (class "Default")
      (node (ref "J4") (pin "373") (pinfunction "373_373") (pintype "passive+no_connect"))
    )
    (net (code "210") (name "unconnected-(J4-Pad375)") (class "Default")
      (node (ref "J4") (pin "375") (pinfunction "375_375") (pintype "passive+no_connect"))
    )
    (net (code "211") (name "unconnected-(J4-Pad376)") (class "Default")
      (node (ref "J4") (pin "376") (pinfunction "376_376") (pintype "passive+no_connect"))
    )
    (net (code "212") (name "unconnected-(J4-Pad378)") (class "Default")
      (node (ref "J4") (pin "378") (pinfunction "378_378") (pintype "passive+no_connect"))
    )
    (net (code "213") (name "unconnected-(J4-Pad379)") (class "Default")
      (node (ref "J4") (pin "379") (pinfunction "379_379") (pintype "passive+no_connect"))
    )
    (net (code "214") (name "unconnected-(J4-Pad382)") (class "Default")
      (node (ref "J4") (pin "382") (pinfunction "382_382") (pintype "passive+no_connect"))
    )
    (net (code "215") (name "unconnected-(J4-Pad383)") (class "Default")
      (node (ref "J4") (pin "383") (pinfunction "383_383") (pintype "passive+no_connect"))
    )
    (net (code "216") (name "unconnected-(J4-Pad385)") (class "Default")
      (node (ref "J4") (pin "385") (pinfunction "385_385") (pintype "passive+no_connect"))
    )
    (net (code "217") (name "unconnected-(J4-Pad386)") (class "Default")
      (node (ref "J4") (pin "386") (pinfunction "386_386") (pintype "passive+no_connect"))
    )
    (net (code "218") (name "unconnected-(J4-Pad388)") (class "Default")
      (node (ref "J4") (pin "388") (pinfunction "388_388") (pintype "passive+no_connect"))
    )
    (net (code "219") (name "unconnected-(J4-Pad389)") (class "Default")
      (node (ref "J4") (pin "389") (pinfunction "389_389") (pintype "passive+no_connect"))
    )
    (net (code "220") (name "unconnected-(J4-Pad392)") (class "Default")
      (node (ref "J4") (pin "392") (pinfunction "392_392") (pintype "passive+no_connect"))
    )
    (net (code "221") (name "unconnected-(J4-Pad393)") (class "Default")
      (node (ref "J4") (pin "393") (pinfunction "393_393") (pintype "passive+no_connect"))
    )
    (net (code "222") (name "unconnected-(J4-Pad395)") (class "Default")
      (node (ref "J4") (pin "395") (pinfunction "395_395") (pintype "passive+no_connect"))
    )
    (net (code "223") (name "unconnected-(J4-Pad396)") (class "Default")
      (node (ref "J4") (pin "396") (pinfunction "396_396") (pintype "passive+no_connect"))
    )
    (net (code "224") (name "unconnected-(J4-Pad398)") (class "Default")
      (node (ref "J4") (pin "398") (pinfunction "398_398") (pintype "passive+no_connect"))
    )
    (net (code "225") (name "unconnected-(J4-Pad399)") (class "Default")
      (node (ref "J4") (pin "399") (pinfunction "399_399") (pintype "passive+no_connect"))
    )
  )
)
